# Sheet1.net
KiCad netlist of a schematic drawn in Altium Designer
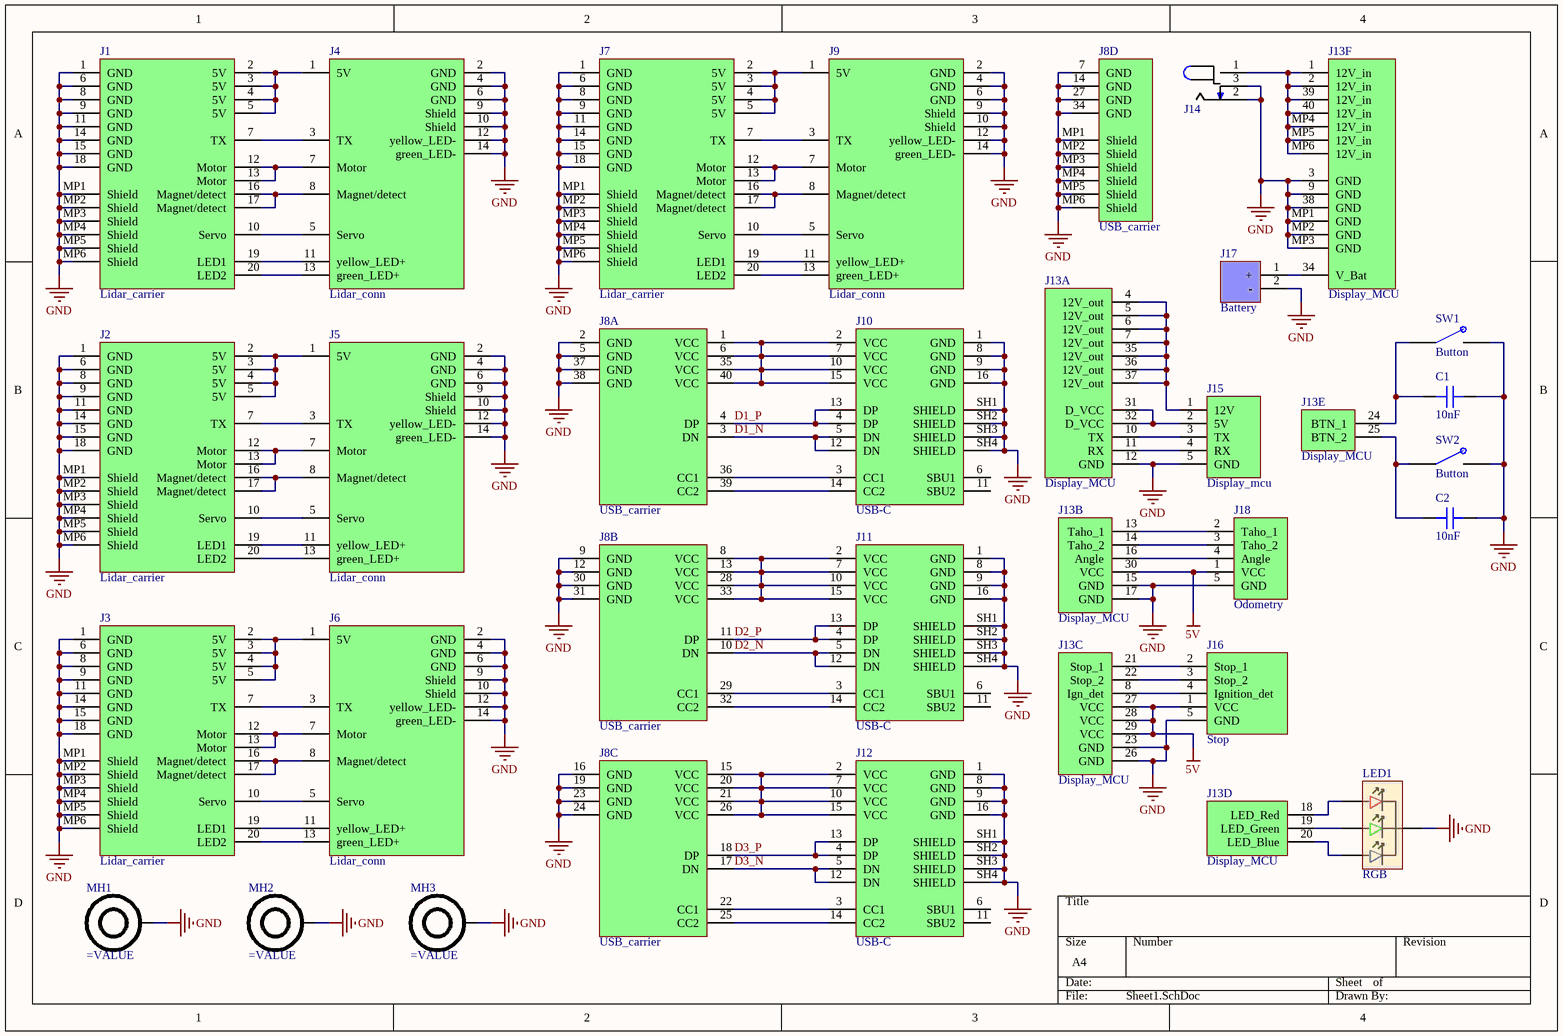
[diagram p0: Sheet1.SchDoc]

(export (version "E")
  (design (tool "Eeschema 10.0.6"))
  (components
    (comp (ref "C1")
      (value "10nF")
      (footprint "CAP 0603")
      (description "SMT Capacitor")
      (libsource (lib "carrier") (part "Capacitor"))
    )
    (comp (ref "C2")
      (value "10nF")
      (footprint "CAP 0603")
      (description "SMT Capacitor")
      (libsource (lib "carrier") (part "Capacitor"))
    )
    (comp (ref "J1")
      (value "Lidar_carrier")
      (footprint "2167000209")
      (libsource (lib "carrier") (part "Lidar_carrier"))
    )
    (comp (ref "J2")
      (value "Lidar_carrier")
      (footprint "2167000209")
      (libsource (lib "carrier") (part "Lidar_carrier"))
    )
    (comp (ref "J3")
      (value "Lidar_carrier")
      (footprint "2167000209")
      (libsource (lib "carrier") (part "Lidar_carrier"))
    )
    (comp (ref "J4")
      (value "Lidar_conn")
      (footprint "MTJ88ARX1FSMLG")
      (libsource (lib "carrier") (part "Lidar_conn"))
    )
    (comp (ref "J5")
      (value "Lidar_conn")
      (footprint "MTJ88ARX1FSMLG")
      (libsource (lib "carrier") (part "Lidar_conn"))
    )
    (comp (ref "J6")
      (value "Lidar_conn")
      (footprint "MTJ88ARX1FSMLG")
      (libsource (lib "carrier") (part "Lidar_conn"))
    )
    (comp (ref "J7")
      (value "Lidar_carrier")
      (footprint "2167000209")
      (libsource (lib "carrier") (part "Lidar_carrier"))
    )
    (comp (ref "J8")
      (value "USB_carrier")
      (footprint "2167000409")
      (libsource (lib "") (part "USB_carrier_1"))
    )
    (comp (ref "J9")
      (value "Lidar_conn")
      (footprint "MTJ88ARX1FSMLG")
      (libsource (lib "carrier") (part "Lidar_conn"))
    )
    (comp (ref "J10")
      (value "USB-C")
      (footprint "AMPHENOL_GSB1C211110DS1HR")
      (libsource (lib "carrier") (part "USB-C"))
    )
    (comp (ref "J11")
      (value "USB-C")
      (footprint "AMPHENOL_GSB1C211110DS1HR")
      (libsource (lib "carrier") (part "USB-C"))
    )
    (comp (ref "J12")
      (value "USB-C")
      (footprint "AMPHENOL_GSB1C211110DS1HR")
      (libsource (lib "carrier") (part "USB-C"))
    )
    (comp (ref "J13")
      (value "Display_MCU")
      (footprint "2167000409")
      (libsource (lib "") (part "AUX_carrier_1"))
    )
    (comp (ref "J14")
      (value "Power Jack")
      (footprint "Power_Jack")
      (description "Power Barrel Connector Jack 2.10mm ID (0.083\"), 5.50mm OD (0.217\") Through Hole, Right Angle")
      (fields (field (name "MFR PART #") "PJ-102A") (field (name "LCSC PART#") "C136744"))
      (libsource (lib "carrier") (part "P_Power Jack"))
    )
    (comp (ref "J15")
      (value "Display_mcu")
      (footprint "SHDRRA5W64P0X250_1X5_1490X1150X610P")
      (libsource (lib "carrier") (part "Display_connector"))
    )
    (comp (ref "J16")
      (value "Stop")
      (footprint "SHDRRA5W64P0X250_1X5_1490X1150X610P")
      (libsource (lib "carrier") (part "Stop_connector"))
    )
    (comp (ref "J17")
      (value "Battery")
      (footprint "BAT_BH-25C-1")
      (libsource (lib "carrier") (part "Battery"))
    )
    (comp (ref "J18")
      (value "Odometry")
      (footprint "SHDRRA5W64P0X250_1X5_1490X1150X610P")
      (libsource (lib "carrier") (part "Odomery_connector"))
    )
    (comp (ref "LED1")
      (value "RGB")
      (footprint "LED_QBL8RGB60D0-2897")
      (fields (field (name "MFR PART #") "NCD1206B1") (field (name "LCSC PART#") "C130717"))
      (libsource (lib "carrier") (part "RGB_LED"))
    )
    (comp (ref "MH1") (value "~") (footprint "SCREW_M3.0") (libsource (lib "carrier") (part "SCREW")))
    (comp (ref "MH2") (value "~") (footprint "SCREW_M3.0") (libsource (lib "carrier") (part "SCREW")))
    (comp (ref "MH3") (value "~") (footprint "SCREW_M3.0") (libsource (lib "carrier") (part "SCREW")))
    (comp (ref "SW1") (value "Button") (footprint "COM10302") (libsource (lib "carrier") (part "Button")))
    (comp (ref "SW2") (value "Button") (footprint "COM10302") (libsource (lib "carrier") (part "Button")))
  )
  (nets
    (net (code "1") (name "/D1_N") (class "Default")
      (node (ref "J10") (pin "12") (pinfunction "DN_12") (pintype "passive"))
      (node (ref "J10") (pin "5") (pinfunction "DN_5") (pintype "passive"))
      (node (ref "J8") (pin "3") (pinfunction "DN_3") (pintype "passive"))
    )
    (net (code "2") (name "/D1_P") (class "Default")
      (node (ref "J10") (pin "13") (pinfunction "DP_13") (pintype "passive"))
      (node (ref "J10") (pin "4") (pinfunction "DP_4") (pintype "passive"))
      (node (ref "J8") (pin "4") (pinfunction "DP_4") (pintype "passive"))
    )
    (net (code "3") (name "/D2_N") (class "Default")
      (node (ref "J11") (pin "12") (pinfunction "DN_12") (pintype "passive"))
      (node (ref "J11") (pin "5") (pinfunction "DN_5") (pintype "passive"))
      (node (ref "J8") (pin "10") (pinfunction "DN_10") (pintype "passive"))
    )
    (net (code "4") (name "/D2_P") (class "Default")
      (node (ref "J11") (pin "13") (pinfunction "DP_13") (pintype "passive"))
      (node (ref "J11") (pin "4") (pinfunction "DP_4") (pintype "passive"))
      (node (ref "J8") (pin "11") (pinfunction "DP_11") (pintype "passive"))
    )
    (net (code "5") (name "/D3_N") (class "Default")
      (node (ref "J12") (pin "12") (pinfunction "DN_12") (pintype "passive"))
      (node (ref "J12") (pin "5") (pinfunction "DN_5") (pintype "passive"))
      (node (ref "J8") (pin "17") (pinfunction "DN_17") (pintype "passive"))
    )
    (net (code "6") (name "/D3_P") (class "Default")
      (node (ref "J12") (pin "13") (pinfunction "DP_13") (pintype "passive"))
      (node (ref "J12") (pin "4") (pinfunction "DP_4") (pintype "passive"))
      (node (ref "J8") (pin "18") (pinfunction "DP_18") (pintype "passive"))
    )
    (net (code "7") (name "5V") (class "Default")
      (node (ref "J13") (pin "27") (pinfunction "VCC_27") (pintype "passive"))
      (node (ref "J13") (pin "28") (pinfunction "VCC_28") (pintype "passive"))
      (node (ref "J13") (pin "29") (pinfunction "VCC_29") (pintype "passive"))
      (node (ref "J13") (pin "30") (pinfunction "VCC_30") (pintype "passive"))
      (node (ref "J16") (pin "1") (pinfunction "VCC_1") (pintype "passive"))
      (node (ref "J18") (pin "1") (pinfunction "VCC_1") (pintype "passive"))
    )
    (net (code "8") (name "GND") (class "Default")
      (node (ref "C1") (pin "2") (pinfunction "2_2") (pintype "passive"))
      (node (ref "C2") (pin "2") (pinfunction "2_2") (pintype "passive"))
      (node (ref "J1") (pin "1") (pinfunction "GND_1") (pintype "passive"))
      (node (ref "J1") (pin "11") (pinfunction "GND_11") (pintype "passive"))
      (node (ref "J1") (pin "14") (pinfunction "GND_14") (pintype "passive"))
      (node (ref "J1") (pin "15") (pinfunction "GND_15") (pintype "passive"))
      (node (ref "J1") (pin "18") (pinfunction "GND_18") (pintype "passive"))
      (node (ref "J1") (pin "6") (pinfunction "GND_6") (pintype "passive"))
      (node (ref "J1") (pin "8") (pinfunction "GND_8") (pintype "passive"))
      (node (ref "J1") (pin "9") (pinfunction "GND_9") (pintype "passive"))
      (node (ref "J1") (pin "MP1") (pinfunction "Shield_MP1") (pintype "passive"))
      (node (ref "J1") (pin "MP2") (pinfunction "Shield_MP2") (pintype "passive"))
      (node (ref "J1") (pin "MP3") (pinfunction "Shield_MP3") (pintype "passive"))
      (node (ref "J1") (pin "MP4") (pinfunction "Shield_MP4") (pintype "passive"))
      (node (ref "J1") (pin "MP5") (pinfunction "Shield_MP5") (pintype "passive"))
      (node (ref "J1") (pin "MP6") (pinfunction "Shield_MP6") (pintype "passive"))
      (node (ref "J10") (pin "1") (pinfunction "GND_1") (pintype "passive"))
      (node (ref "J10") (pin "16") (pinfunction "GND_16") (pintype "passive"))
      (node (ref "J10") (pin "8") (pinfunction "GND_8") (pintype "passive"))
      (node (ref "J10") (pin "9") (pinfunction "GND_9") (pintype "passive"))
      (node (ref "J10") (pin "SH1") (pinfunction "SHIELD_SH1") (pintype "passive"))
      (node (ref "J10") (pin "SH2") (pinfunction "SHIELD_SH2") (pintype "passive"))
      (node (ref "J10") (pin "SH3") (pinfunction "SHIELD_SH3") (pintype "passive"))
      (node (ref "J10") (pin "SH4") (pinfunction "SHIELD_SH4") (pintype "passive"))
      (node (ref "J11") (pin "1") (pinfunction "GND_1") (pintype "passive"))
      (node (ref "J11") (pin "16") (pinfunction "GND_16") (pintype "passive"))
      (node (ref "J11") (pin "8") (pinfunction "GND_8") (pintype "passive"))
      (node (ref "J11") (pin "9") (pinfunction "GND_9") (pintype "passive"))
      (node (ref "J11") (pin "SH1") (pinfunction "SHIELD_SH1") (pintype "passive"))
      (node (ref "J11") (pin "SH2") (pinfunction "SHIELD_SH2") (pintype "passive"))
      (node (ref "J11") (pin "SH3") (pinfunction "SHIELD_SH3") (pintype "passive"))
      (node (ref "J11") (pin "SH4") (pinfunction "SHIELD_SH4") (pintype "passive"))
      (node (ref "J12") (pin "1") (pinfunction "GND_1") (pintype "passive"))
      (node (ref "J12") (pin "16") (pinfunction "GND_16") (pintype "passive"))
      (node (ref "J12") (pin "8") (pinfunction "GND_8") (pintype "passive"))
      (node (ref "J12") (pin "9") (pinfunction "GND_9") (pintype "passive"))
      (node (ref "J12") (pin "SH1") (pinfunction "SHIELD_SH1") (pintype "passive"))
      (node (ref "J12") (pin "SH2") (pinfunction "SHIELD_SH2") (pintype "passive"))
      (node (ref "J12") (pin "SH3") (pinfunction "SHIELD_SH3") (pintype "passive"))
      (node (ref "J12") (pin "SH4") (pinfunction "SHIELD_SH4") (pintype "passive"))
      (node (ref "J13") (pin "12") (pinfunction "GND_12") (pintype "passive"))
      (node (ref "J13") (pin "15") (pinfunction "GND_15") (pintype "passive"))
      (node (ref "J13") (pin "17") (pinfunction "GND_17") (pintype "passive"))
      (node (ref "J13") (pin "23") (pinfunction "GND_23") (pintype "passive"))
      (node (ref "J13") (pin "26") (pinfunction "GND_26") (pintype "passive"))
      (node (ref "J13") (pin "3") (pinfunction "GND_3") (pintype "passive"))
      (node (ref "J13") (pin "38") (pinfunction "GND_38") (pintype "passive"))
      (node (ref "J13") (pin "9") (pinfunction "GND_9") (pintype "passive"))
      (node (ref "J13") (pin "MP1") (pinfunction "GND_MP1") (pintype "passive"))
      (node (ref "J13") (pin "MP2") (pinfunction "GND_MP2") (pintype "passive"))
      (node (ref "J13") (pin "MP3") (pinfunction "GND_MP3") (pintype "passive"))
      (node (ref "J14") (pin "2") (pinfunction "2_2") (pintype "power_in"))
      (node (ref "J14") (pin "3") (pinfunction "3_3") (pintype "power_in"))
      (node (ref "J15") (pin "5") (pinfunction "GND_5") (pintype "passive"))
      (node (ref "J16") (pin "5") (pinfunction "GND_5") (pintype "passive"))
      (node (ref "J17") (pin "2") (pinfunction "-_2") (pintype "passive"))
      (node (ref "J18") (pin "5") (pinfunction "GND_5") (pintype "passive"))
      (node (ref "J2") (pin "1") (pinfunction "GND_1") (pintype "passive"))
      (node (ref "J2") (pin "11") (pinfunction "GND_11") (pintype "passive"))
      (node (ref "J2") (pin "14") (pinfunction "GND_14") (pintype "passive"))
      (node (ref "J2") (pin "15") (pinfunction "GND_15") (pintype "passive"))
      (node (ref "J2") (pin "18") (pinfunction "GND_18") (pintype "passive"))
      (node (ref "J2") (pin "6") (pinfunction "GND_6") (pintype "passive"))
      (node (ref "J2") (pin "8") (pinfunction "GND_8") (pintype "passive"))
      (node (ref "J2") (pin "9") (pinfunction "GND_9") (pintype "passive"))
      (node (ref "J2") (pin "MP1") (pinfunction "Shield_MP1") (pintype "passive"))
      (node (ref "J2") (pin "MP2") (pinfunction "Shield_MP2") (pintype "passive"))
      (node (ref "J2") (pin "MP3") (pinfunction "Shield_MP3") (pintype "passive"))
      (node (ref "J2") (pin "MP4") (pinfunction "Shield_MP4") (pintype "passive"))
      (node (ref "J2") (pin "MP5") (pinfunction "Shield_MP5") (pintype "passive"))
      (node (ref "J2") (pin "MP6") (pinfunction "Shield_MP6") (pintype "passive"))
      (node (ref "J3") (pin "1") (pinfunction "GND_1") (pintype "passive"))
      (node (ref "J3") (pin "11") (pinfunction "GND_11") (pintype "passive"))
      (node (ref "J3") (pin "14") (pinfunction "GND_14") (pintype "passive"))
      (node (ref "J3") (pin "15") (pinfunction "GND_15") (pintype "passive"))
      (node (ref "J3") (pin "18") (pinfunction "GND_18") (pintype "passive"))
      (node (ref "J3") (pin "6") (pinfunction "GND_6") (pintype "passive"))
      (node (ref "J3") (pin "8") (pinfunction "GND_8") (pintype "passive"))
      (node (ref "J3") (pin "9") (pinfunction "GND_9") (pintype "passive"))
      (node (ref "J3") (pin "MP1") (pinfunction "Shield_MP1") (pintype "passive"))
      (node (ref "J3") (pin "MP2") (pinfunction "Shield_MP2") (pintype "passive"))
      (node (ref "J3") (pin "MP3") (pinfunction "Shield_MP3") (pintype "passive"))
      (node (ref "J3") (pin "MP4") (pinfunction "Shield_MP4") (pintype "passive"))
      (node (ref "J3") (pin "MP5") (pinfunction "Shield_MP5") (pintype "passive"))
      (node (ref "J3") (pin "MP6") (pinfunction "Shield_MP6") (pintype "passive"))
      (node (ref "J4") (pin "10") (pinfunction "Shield_10") (pintype "passive"))
      (node (ref "J4") (pin "12") (pinfunction "yellow_LED-_12") (pintype "passive"))
      (node (ref "J4") (pin "14") (pinfunction "green_LED-_14") (pintype "passive"))
      (node (ref "J4") (pin "2") (pinfunction "GND_2") (pintype "passive"))
      (node (ref "J4") (pin "4") (pinfunction "GND_4") (pintype "passive"))
      (node (ref "J4") (pin "6") (pinfunction "GND_6") (pintype "passive"))
      (node (ref "J4") (pin "9") (pinfunction "Shield_9") (pintype "passive"))
      (node (ref "J5") (pin "10") (pinfunction "Shield_10") (pintype "passive"))
      (node (ref "J5") (pin "12") (pinfunction "yellow_LED-_12") (pintype "passive"))
      (node (ref "J5") (pin "14") (pinfunction "green_LED-_14") (pintype "passive"))
      (node (ref "J5") (pin "2") (pinfunction "GND_2") (pintype "passive"))
      (node (ref "J5") (pin "4") (pinfunction "GND_4") (pintype "passive"))
      (node (ref "J5") (pin "6") (pinfunction "GND_6") (pintype "passive"))
      (node (ref "J5") (pin "9") (pinfunction "Shield_9") (pintype "passive"))
      (node (ref "J6") (pin "10") (pinfunction "Shield_10") (pintype "passive"))
      (node (ref "J6") (pin "12") (pinfunction "yellow_LED-_12") (pintype "passive"))
      (node (ref "J6") (pin "14") (pinfunction "green_LED-_14") (pintype "passive"))
      (node (ref "J6") (pin "2") (pinfunction "GND_2") (pintype "passive"))
      (node (ref "J6") (pin "4") (pinfunction "GND_4") (pintype "passive"))
      (node (ref "J6") (pin "6") (pinfunction "GND_6") (pintype "passive"))
      (node (ref "J6") (pin "9") (pinfunction "Shield_9") (pintype "passive"))
      (node (ref "J7") (pin "1") (pinfunction "GND_1") (pintype "passive"))
      (node (ref "J7") (pin "11") (pinfunction "GND_11") (pintype "passive"))
      (node (ref "J7") (pin "14") (pinfunction "GND_14") (pintype "passive"))
      (node (ref "J7") (pin "15") (pinfunction "GND_15") (pintype "passive"))
      (node (ref "J7") (pin "18") (pinfunction "GND_18") (pintype "passive"))
      (node (ref "J7") (pin "6") (pinfunction "GND_6") (pintype "passive"))
      (node (ref "J7") (pin "8") (pinfunction "GND_8") (pintype "passive"))
      (node (ref "J7") (pin "9") (pinfunction "GND_9") (pintype "passive"))
      (node (ref "J7") (pin "MP1") (pinfunction "Shield_MP1") (pintype "passive"))
      (node (ref "J7") (pin "MP2") (pinfunction "Shield_MP2") (pintype "passive"))
      (node (ref "J7") (pin "MP3") (pinfunction "Shield_MP3") (pintype "passive"))
      (node (ref "J7") (pin "MP4") (pinfunction "Shield_MP4") (pintype "passive"))
      (node (ref "J7") (pin "MP5") (pinfunction "Shield_MP5") (pintype "passive"))
      (node (ref "J7") (pin "MP6") (pinfunction "Shield_MP6") (pintype "passive"))
      (node (ref "J8") (pin "12") (pinfunction "GND_12") (pintype "passive"))
      (node (ref "J8") (pin "14") (pinfunction "GND_14") (pintype "passive"))
      (node (ref "J8") (pin "16") (pinfunction "GND_16") (pintype "passive"))
      (node (ref "J8") (pin "19") (pinfunction "GND_19") (pintype "passive"))
      (node (ref "J8") (pin "2") (pinfunction "GND_2") (pintype "passive"))
      (node (ref "J8") (pin "23") (pinfunction "GND_23") (pintype "passive"))
      (node (ref "J8") (pin "24") (pinfunction "GND_24") (pintype "passive"))
      (node (ref "J8") (pin "27") (pinfunction "GND_27") (pintype "passive"))
      (node (ref "J8") (pin "30") (pinfunction "GND_30") (pintype "passive"))
      (node (ref "J8") (pin "31") (pinfunction "GND_31") (pintype "passive"))
      (node (ref "J8") (pin "34") (pinfunction "GND_34") (pintype "passive"))
      (node (ref "J8") (pin "37") (pinfunction "GND_37") (pintype "passive"))
      (node (ref "J8") (pin "38") (pinfunction "GND_38") (pintype "passive"))
      (node (ref "J8") (pin "5") (pinfunction "GND_5") (pintype "passive"))
      (node (ref "J8") (pin "7") (pinfunction "GND_7") (pintype "passive"))
      (node (ref "J8") (pin "9") (pinfunction "GND_9") (pintype "passive"))
      (node (ref "J8") (pin "MP1") (pinfunction "Shield_MP1") (pintype "passive"))
      (node (ref "J8") (pin "MP2") (pinfunction "Shield_MP2") (pintype "passive"))
      (node (ref "J8") (pin "MP3") (pinfunction "Shield_MP3") (pintype "passive"))
      (node (ref "J8") (pin "MP4") (pinfunction "Shield_MP4") (pintype "passive"))
      (node (ref "J8") (pin "MP5") (pinfunction "Shield_MP5") (pintype "passive"))
      (node (ref "J8") (pin "MP6") (pinfunction "Shield_MP6") (pintype "passive"))
      (node (ref "J9") (pin "10") (pinfunction "Shield_10") (pintype "passive"))
      (node (ref "J9") (pin "12") (pinfunction "yellow_LED-_12") (pintype "passive"))
      (node (ref "J9") (pin "14") (pinfunction "green_LED-_14") (pintype "passive"))
      (node (ref "J9") (pin "2") (pinfunction "GND_2") (pintype "passive"))
      (node (ref "J9") (pin "4") (pinfunction "GND_4") (pintype "passive"))
      (node (ref "J9") (pin "6") (pinfunction "GND_6") (pintype "passive"))
      (node (ref "J9") (pin "9") (pinfunction "Shield_9") (pintype "passive"))
      (node (ref "LED1") (pin "2") (pinfunction "Catode_2") (pintype "passive"))
      (node (ref "MH1") (pin "1") (pinfunction "1_1") (pintype "passive"))
      (node (ref "MH2") (pin "1") (pinfunction "1_1") (pintype "passive"))
      (node (ref "MH3") (pin "1") (pinfunction "1_1") (pintype "passive"))
      (node (ref "SW1") (pin "2") (pinfunction "2_2") (pintype "passive"))
      (node (ref "SW2") (pin "2") (pinfunction "2_2") (pintype "passive"))
    )
    (net (code "9") (name "Net-(J1-LED1)") (class "Default")
      (node (ref "J1") (pin "19") (pinfunction "LED1_19") (pintype "passive"))
      (node (ref "J4") (pin "11") (pinfunction "yellow_LED+_11") (pintype "passive"))
    )
    (net (code "10") (name "Net-(J1-LED2)") (class "Default")
      (node (ref "J1") (pin "20") (pinfunction "LED2_20") (pintype "passive"))
      (node (ref "J4") (pin "13") (pinfunction "green_LED+_13") (pintype "passive"))
    )
    (net (code "11") (name "Net-(J1-Servo)") (class "Default")
      (node (ref "J1") (pin "10") (pinfunction "Servo_10") (pintype "passive"))
      (node (ref "J4") (pin "5") (pinfunction "Servo_5") (pintype "passive"))
    )
    (net (code "12") (name "Net-(J1-TX)") (class "Default")
      (node (ref "J1") (pin "7") (pinfunction "TX_7") (pintype "passive"))
      (node (ref "J4") (pin "3") (pinfunction "TX_3") (pintype "passive"))
    )
    (net (code "13") (name "Net-(J2-LED1)") (class "Default")
      (node (ref "J2") (pin "19") (pinfunction "LED1_19") (pintype "passive"))
      (node (ref "J5") (pin "11") (pinfunction "yellow_LED+_11") (pintype "passive"))
    )
    (net (code "14") (name "Net-(J2-LED2)") (class "Default")
      (node (ref "J2") (pin "20") (pinfunction "LED2_20") (pintype "passive"))
      (node (ref "J5") (pin "13") (pinfunction "green_LED+_13") (pintype "passive"))
    )
    (net (code "15") (name "Net-(J2-Servo)") (class "Default")
      (node (ref "J2") (pin "10") (pinfunction "Servo_10") (pintype "passive"))
      (node (ref "J5") (pin "5") (pinfunction "Servo_5") (pintype "passive"))
    )
    (net (code "16") (name "Net-(J2-TX)") (class "Default")
      (node (ref "J2") (pin "7") (pinfunction "TX_7") (pintype "passive"))
      (node (ref "J5") (pin "3") (pinfunction "TX_3") (pintype "passive"))
    )
    (net (code "17") (name "Net-(J3-LED1)") (class "Default")
      (node (ref "J3") (pin "19") (pinfunction "LED1_19") (pintype "passive"))
      (node (ref "J6") (pin "11") (pinfunction "yellow_LED+_11") (pintype "passive"))
    )
    (net (code "18") (name "Net-(J3-LED2)") (class "Default")
      (node (ref "J3") (pin "20") (pinfunction "LED2_20") (pintype "passive"))
      (node (ref "J6") (pin "13") (pinfunction "green_LED+_13") (pintype "passive"))
    )
    (net (code "19") (name "Net-(J3-Servo)") (class "Default")
      (node (ref "J3") (pin "10") (pinfunction "Servo_10") (pintype "passive"))
      (node (ref "J6") (pin "5") (pinfunction "Servo_5") (pintype "passive"))
    )
    (net (code "20") (name "Net-(J3-TX)") (class "Default")
      (node (ref "J3") (pin "7") (pinfunction "TX_7") (pintype "passive"))
      (node (ref "J6") (pin "3") (pinfunction "TX_3") (pintype "passive"))
    )
    (net (code "21") (name "Net-(J4-5V)") (class "Default")
      (node (ref "J1") (pin "2") (pinfunction "5V_2") (pintype "passive"))
      (node (ref "J1") (pin "3") (pinfunction "5V_3") (pintype "passive"))
      (node (ref "J1") (pin "4") (pinfunction "5V_4") (pintype "passive"))
      (node (ref "J1") (pin "5") (pinfunction "5V_5") (pintype "passive"))
      (node (ref "J4") (pin "1") (pinfunction "5V_1") (pintype "passive"))
    )
    (net (code "22") (name "Net-(J4-Magnet{slash}detect)") (class "Default")
      (node (ref "J1") (pin "16") (pinfunction "Magnet/detect_16") (pintype "passive"))
      (node (ref "J1") (pin "17") (pinfunction "Magnet/detect_17") (pintype "passive"))
      (node (ref "J4") (pin "8") (pinfunction "Magnet/detect_8") (pintype "passive"))
    )
    (net (code "23") (name "Net-(J4-Motor)") (class "Default")
      (node (ref "J1") (pin "12") (pinfunction "Motor_12") (pintype "passive"))
      (node (ref "J1") (pin "13") (pinfunction "Motor_13") (pintype "passive"))
      (node (ref "J4") (pin "7") (pinfunction "Motor_7") (pintype "passive"))
    )
    (net (code "24") (name "Net-(J5-5V)") (class "Default")
      (node (ref "J2") (pin "2") (pinfunction "5V_2") (pintype "passive"))
      (node (ref "J2") (pin "3") (pinfunction "5V_3") (pintype "passive"))
      (node (ref "J2") (pin "4") (pinfunction "5V_4") (pintype "passive"))
      (node (ref "J2") (pin "5") (pinfunction "5V_5") (pintype "passive"))
      (node (ref "J5") (pin "1") (pinfunction "5V_1") (pintype "passive"))
    )
    (net (code "25") (name "Net-(J5-Magnet{slash}detect)") (class "Default")
      (node (ref "J2") (pin "16") (pinfunction "Magnet/detect_16") (pintype "passive"))
      (node (ref "J2") (pin "17") (pinfunction "Magnet/detect_17") (pintype "passive"))
      (node (ref "J5") (pin "8") (pinfunction "Magnet/detect_8") (pintype "passive"))
    )
    (net (code "26") (name "Net-(J5-Motor)") (class "Default")
      (node (ref "J2") (pin "12") (pinfunction "Motor_12") (pintype "passive"))
      (node (ref "J2") (pin "13") (pinfunction "Motor_13") (pintype "passive"))
      (node (ref "J5") (pin "7") (pinfunction "Motor_7") (pintype "passive"))
    )
    (net (code "27") (name "Net-(J6-5V)") (class "Default")
      (node (ref "J3") (pin "2") (pinfunction "5V_2") (pintype "passive"))
      (node (ref "J3") (pin "3") (pinfunction "5V_3") (pintype "passive"))
      (node (ref "J3") (pin "4") (pinfunction "5V_4") (pintype "passive"))
      (node (ref "J3") (pin "5") (pinfunction "5V_5") (pintype "passive"))
      (node (ref "J6") (pin "1") (pinfunction "5V_1") (pintype "passive"))
    )
    (net (code "28") (name "Net-(J6-Magnet{slash}detect)") (class "Default")
      (node (ref "J3") (pin "16") (pinfunction "Magnet/detect_16") (pintype "passive"))
      (node (ref "J3") (pin "17") (pinfunction "Magnet/detect_17") (pintype "passive"))
      (node (ref "J6") (pin "8") (pinfunction "Magnet/detect_8") (pintype "passive"))
    )
    (net (code "29") (name "Net-(J6-Motor)") (class "Default")
      (node (ref "J3") (pin "12") (pinfunction "Motor_12") (pintype "passive"))
      (node (ref "J3") (pin "13") (pinfunction "Motor_13") (pintype "passive"))
      (node (ref "J6") (pin "7") (pinfunction "Motor_7") (pintype "passive"))
    )
    (net (code "30") (name "Net-(J7-LED1)") (class "Default")
      (node (ref "J7") (pin "19") (pinfunction "LED1_19") (pintype "passive"))
      (node (ref "J9") (pin "11") (pinfunction "yellow_LED+_11") (pintype "passive"))
    )
    (net (code "31") (name "Net-(J7-LED2)") (class "Default")
      (node (ref "J7") (pin "20") (pinfunction "LED2_20") (pintype "passive"))
      (node (ref "J9") (pin "13") (pinfunction "green_LED+_13") (pintype "passive"))
    )
    (net (code "32") (name "Net-(J7-Servo)") (class "Default")
      (node (ref "J7") (pin "10") (pinfunction "Servo_10") (pintype "passive"))
      (node (ref "J9") (pin "5") (pinfunction "Servo_5") (pintype "passive"))
    )
    (net (code "33") (name "Net-(J7-TX)") (class "Default")
      (node (ref "J7") (pin "7") (pinfunction "TX_7") (pintype "passive"))
      (node (ref "J9") (pin "3") (pinfunction "TX_3") (pintype "passive"))
    )
    (net (code "34") (name "Net-(J9-5V)") (class "Default")
      (node (ref "J7") (pin "2") (pinfunction "5V_2") (pintype "passive"))
      (node (ref "J7") (pin "3") (pinfunction "5V_3") (pintype "passive"))
      (node (ref "J7") (pin "4") (pinfunction "5V_4") (pintype "passive"))
      (node (ref "J7") (pin "5") (pinfunction "5V_5") (pintype "passive"))
      (node (ref "J9") (pin "1") (pinfunction "5V_1") (pintype "passive"))
    )
    (net (code "35") (name "Net-(J9-Magnet{slash}detect)") (class "Default")
      (node (ref "J7") (pin "16") (pinfunction "Magnet/detect_16") (pintype "passive"))
      (node (ref "J7") (pin "17") (pinfunction "Magnet/detect_17") (pintype "passive"))
      (node (ref "J9") (pin "8") (pinfunction "Magnet/detect_8") (pintype "passive"))
    )
    (net (code "36") (name "Net-(J9-Motor)") (class "Default")
      (node (ref "J7") (pin "12") (pinfunction "Motor_12") (pintype "passive"))
      (node (ref "J7") (pin "13") (pinfunction "Motor_13") (pintype "passive"))
      (node (ref "J9") (pin "7") (pinfunction "Motor_7") (pintype "passive"))
    )
    (net (code "37") (name "Net-(J10-CC1)") (class "Default")
      (node (ref "J10") (pin "3") (pinfunction "CC1_3") (pintype "passive"))
      (node (ref "J8") (pin "36") (pinfunction "CC1_36") (pintype "passive"))
    )
    (net (code "38") (name "Net-(J10-CC2)") (class "Default")
      (node (ref "J10") (pin "14") (pinfunction "CC2_14") (pintype "passive"))
      (node (ref "J8") (pin "39") (pinfunction "CC2_39") (pintype "passive"))
    )
    (net (code "39") (name "Net-(J10-VCC-Pad10)") (class "Default")
      (node (ref "J10") (pin "10") (pinfunction "VCC_10") (pintype "passive"))
      (node (ref "J10") (pin "15") (pinfunction "VCC_15") (pintype "passive"))
      (node (ref "J10") (pin "2") (pinfunction "VCC_2") (pintype "passive"))
      (node (ref "J10") (pin "7") (pinfunction "VCC_7") (pintype "passive"))
      (node (ref "J8") (pin "1") (pinfunction "VCC_1") (pintype "passive"))
      (node (ref "J8") (pin "35") (pinfunction "VCC_35") (pintype "passive"))
      (node (ref "J8") (pin "40") (pinfunction "VCC_40") (pintype "passive"))
      (node (ref "J8") (pin "6") (pinfunction "VCC_6") (pintype "passive"))
    )
    (net (code "40") (name "Net-(J11-CC1)") (class "Default")
      (node (ref "J11") (pin "3") (pinfunction "CC1_3") (pintype "passive"))
      (node (ref "J8") (pin "29") (pinfunction "CC1_29") (pintype "passive"))
    )
    (net (code "41") (name "Net-(J11-CC2)") (class "Default")
      (node (ref "J11") (pin "14") (pinfunction "CC2_14") (pintype "passive"))
      (node (ref "J8") (pin "32") (pinfunction "CC2_32") (pintype "passive"))
    )
    (net (code "42") (name "Net-(J11-VCC-Pad10)") (class "Default")
      (node (ref "J11") (pin "10") (pinfunction "VCC_10") (pintype "passive"))
      (node (ref "J11") (pin "15") (pinfunction "VCC_15") (pintype "passive"))
      (node (ref "J11") (pin "2") (pinfunction "VCC_2") (pintype "passive"))
      (node (ref "J11") (pin "7") (pinfunction "VCC_7") (pintype "passive"))
      (node (ref "J8") (pin "13") (pinfunction "VCC_13") (pintype "passive"))
      (node (ref "J8") (pin "28") (pinfunction "VCC_28") (pintype "passive"))
      (node (ref "J8") (pin "33") (pinfunction "VCC_33") (pintype "passive"))
      (node (ref "J8") (pin "8") (pinfunction "VCC_8") (pintype "passive"))
    )
    (net (code "43") (name "Net-(J12-CC1)") (class "Default")
      (node (ref "J12") (pin "3") (pinfunction "CC1_3") (pintype "passive"))
      (node (ref "J8") (pin "22") (pinfunction "CC1_22") (pintype "passive"))
    )
    (net (code "44") (name "Net-(J12-CC2)") (class "Default")
      (node (ref "J12") (pin "14") (pinfunction "CC2_14") (pintype "passive"))
      (node (ref "J8") (pin "25") (pinfunction "CC2_25") (pintype "passive"))
    )
    (net (code "45") (name "Net-(J12-VCC-Pad10)") (class "Default")
      (node (ref "J12") (pin "10") (pinfunction "VCC_10") (pintype "passive"))
      (node (ref "J12") (pin "15") (pinfunction "VCC_15") (pintype "passive"))
      (node (ref "J12") (pin "2") (pinfunction "VCC_2") (pintype "passive"))
      (node (ref "J12") (pin "7") (pinfunction "VCC_7") (pintype "passive"))
      (node (ref "J8") (pin "15") (pinfunction "VCC_15") (pintype "passive"))
      (node (ref "J8") (pin "20") (pinfunction "VCC_20") (pintype "passive"))
      (node (ref "J8") (pin "21") (pinfunction "VCC_21") (pintype "passive"))
      (node (ref "J8") (pin "26") (pinfunction "VCC_26") (pintype "passive"))
    )
    (net (code "46") (name "Net-(J13A-RX)") (class "Default")
      (node (ref "J13") (pin "11") (pinfunction "RX_11") (pintype "passive"))
      (node (ref "J15") (pin "4") (pinfunction "RX_4") (pintype "passive"))
    )
    (net (code "47") (name "Net-(J13A-TX)") (class "Default")
      (node (ref "J13") (pin "10") (pinfunction "TX_10") (pintype "passive"))
      (node (ref "J15") (pin "3") (pinfunction "TX_3") (pintype "passive"))
    )
    (net (code "48") (name "Net-(J13B-Angle)") (class "Default")
      (node (ref "J13") (pin "16") (pinfunction "Angle_16") (pintype "passive"))
      (node (ref "J18") (pin "4") (pinfunction "Angle_4") (pintype "passive"))
    )
    (net (code "49") (name "Net-(J13B-Taho_1)") (class "Default")
      (node (ref "J13") (pin "13") (pinfunction "Taho_1_13") (pintype "passive"))
      (node (ref "J18") (pin "2") (pinfunction "Taho_1_2") (pintype "passive"))
    )
    (net (code "50") (name "Net-(J13B-Taho_2)") (class "Default")
      (node (ref "J13") (pin "14") (pinfunction "Taho_2_14") (pintype "passive"))
      (node (ref "J18") (pin "3") (pinfunction "Taho_2_3") (pintype "passive"))
    )
    (net (code "51") (name "Net-(J13C-Ign_det)") (class "Default")
      (node (ref "J13") (pin "8") (pinfunction "Ign_det_8") (pintype "passive"))
      (node (ref "J16") (pin "4") (pinfunction "Ignition_det_4") (pintype "passive"))
    )
    (net (code "52") (name "Net-(J13C-Stop_1)") (class "Default")
      (node (ref "J13") (pin "21") (pinfunction "Stop_1_21") (pintype "passive"))
      (node (ref "J16") (pin "2") (pinfunction "Stop_1_2") (pintype "passive"))
    )
    (net (code "53") (name "Net-(J13C-Stop_2)") (class "Default")
      (node (ref "J13") (pin "22") (pinfunction "Stop_2_22") (pintype "passive"))
      (node (ref "J16") (pin "3") (pinfunction "Stop_2_3") (pintype "passive"))
    )
    (net (code "54") (name "Net-(J13D-LED_Blue)") (class "Default")
      (node (ref "J13") (pin "20") (pinfunction "LED_Blue_20") (pintype "passive"))
      (node (ref "LED1") (pin "4") (pinfunction "B_4") (pintype "passive"))
    )
    (net (code "55") (name "Net-(J13D-LED_Green)") (class "Default")
      (node (ref "J13") (pin "19") (pinfunction "LED_Green_19") (pintype "passive"))
      (node (ref "LED1") (pin "3") (pinfunction "G_3") (pintype "passive"))
    )
    (net (code "56") (name "Net-(J13D-LED_Red)") (class "Default")
      (node (ref "J13") (pin "18") (pinfunction "LED_Red_18") (pintype "passive"))
      (node (ref "LED1") (pin "1") (pinfunction "R_1") (pintype "passive"))
    )
    (net (code "57") (name "Net-(J13E-BTN_1)") (class "Default")
      (node (ref "C1") (pin "1") (pinfunction "1_1") (pintype "passive"))
      (node (ref "J13") (pin "24") (pinfunction "BTN_1_24") (pintype "passive"))
      (node (ref "SW1") (pin "1") (pinfunction "1_1") (pintype "passive"))
    )
    (net (code "58") (name "Net-(J13E-BTN_2)") (class "Default")
      (node (ref "C2") (pin "1") (pinfunction "1_1") (pintype "passive"))
      (node (ref "J13") (pin "25") (pinfunction "BTN_2_25") (pintype "passive"))
      (node (ref "SW2") (pin "1") (pinfunction "1_1") (pintype "passive"))
    )
    (net (code "59") (name "Net-(J13F-12V_in-Pad1)") (class "Default")
      (node (ref "J13") (pin "1") (pinfunction "12V_in_1") (pintype "passive"))
      (node (ref "J13") (pin "2") (pinfunction "12V_in_2") (pintype "passive"))
      (node (ref "J13") (pin "39") (pinfunction "12V_in_39") (pintype "passive"))
      (node (ref "J13") (pin "40") (pinfunction "12V_in_40") (pintype "passive"))
      (node (ref "J13") (pin "MP4") (pinfunction "12V_in_MP4") (pintype "passive"))
      (node (ref "J13") (pin "MP5") (pinfunction "12V_in_MP5") (pintype "passive"))
      (node (ref "J13") (pin "MP6") (pinfunction "12V_in_MP6") (pintype "passive"))
      (node (ref "J14") (pin "1") (pinfunction "1_1") (pintype "power_in"))
    )
    (net (code "60") (name "Net-(J13F-V_Bat)") (class "Default")
      (node (ref "J13") (pin "34") (pinfunction "V_Bat_34") (pintype "passive"))
      (node (ref "J17") (pin "1") (pinfunction "+_1") (pintype "passive"))
    )
    (net (code "61") (name "Net-(J15-5V)") (class "Default")
      (node (ref "J13") (pin "31") (pinfunction "D_VCC_31") (pintype "passive"))
      (node (ref "J13") (pin "32") (pinfunction "D_VCC_32") (pintype "passive"))
      (node (ref "J15") (pin "2") (pinfunction "5V_2") (pintype "passive"))
    )
    (net (code "62") (name "Net-(J15-12V)") (class "Default")
      (node (ref "J13") (pin "35") (pinfunction "12V_out_35") (pintype "passive"))
      (node (ref "J13") (pin "36") (pinfunction "12V_out_36") (pintype "passive"))
      (node (ref "J13") (pin "37") (pinfunction "12V_out_37") (pintype "passive"))
      (node (ref "J13") (pin "4") (pinfunction "12V_out_4") (pintype "passive"))
      (node (ref "J13") (pin "5") (pinfunction "12V_out_5") (pintype "passive"))
      (node (ref "J13") (pin "6") (pinfunction "12V_out_6") (pintype "passive"))
      (node (ref "J13") (pin "7") (pinfunction "12V_out_7") (pintype "passive"))
      (node (ref "J15") (pin "1") (pinfunction "12V_1") (pintype "passive"))
    )
    (net (code "63") (name "unconnected-(J10-SBU1-Pad6)") (class "Default")
      (node (ref "J10") (pin "6") (pinfunction "SBU1_6") (pintype "passive"))
    )
    (net (code "64") (name "unconnected-(J10-SBU2-Pad11)") (class "Default")
      (node (ref "J10") (pin "11") (pinfunction "SBU2_11") (pintype "passive"))
    )
    (net (code "65") (name "unconnected-(J11-SBU1-Pad6)") (class "Default")
      (node (ref "J11") (pin "6") (pinfunction "SBU1_6") (pintype "passive"))
    )
    (net (code "66") (name "unconnected-(J11-SBU2-Pad11)") (class "Default")
      (node (ref "J11") (pin "11") (pinfunction "SBU2_11") (pintype "passive"))
    )
    (net (code "67") (name "unconnected-(J12-SBU1-Pad6)") (class "Default")
      (node (ref "J12") (pin "6") (pinfunction "SBU1_6") (pintype "passive"))
    )
    (net (code "68") (name "unconnected-(J12-SBU2-Pad11)") (class "Default")
      (node (ref "J12") (pin "11") (pinfunction "SBU2_11") (pintype "passive"))
    )
  )
)
